# ClockDelay.net
KiCad netlist of a schematic drawn in EAGLE
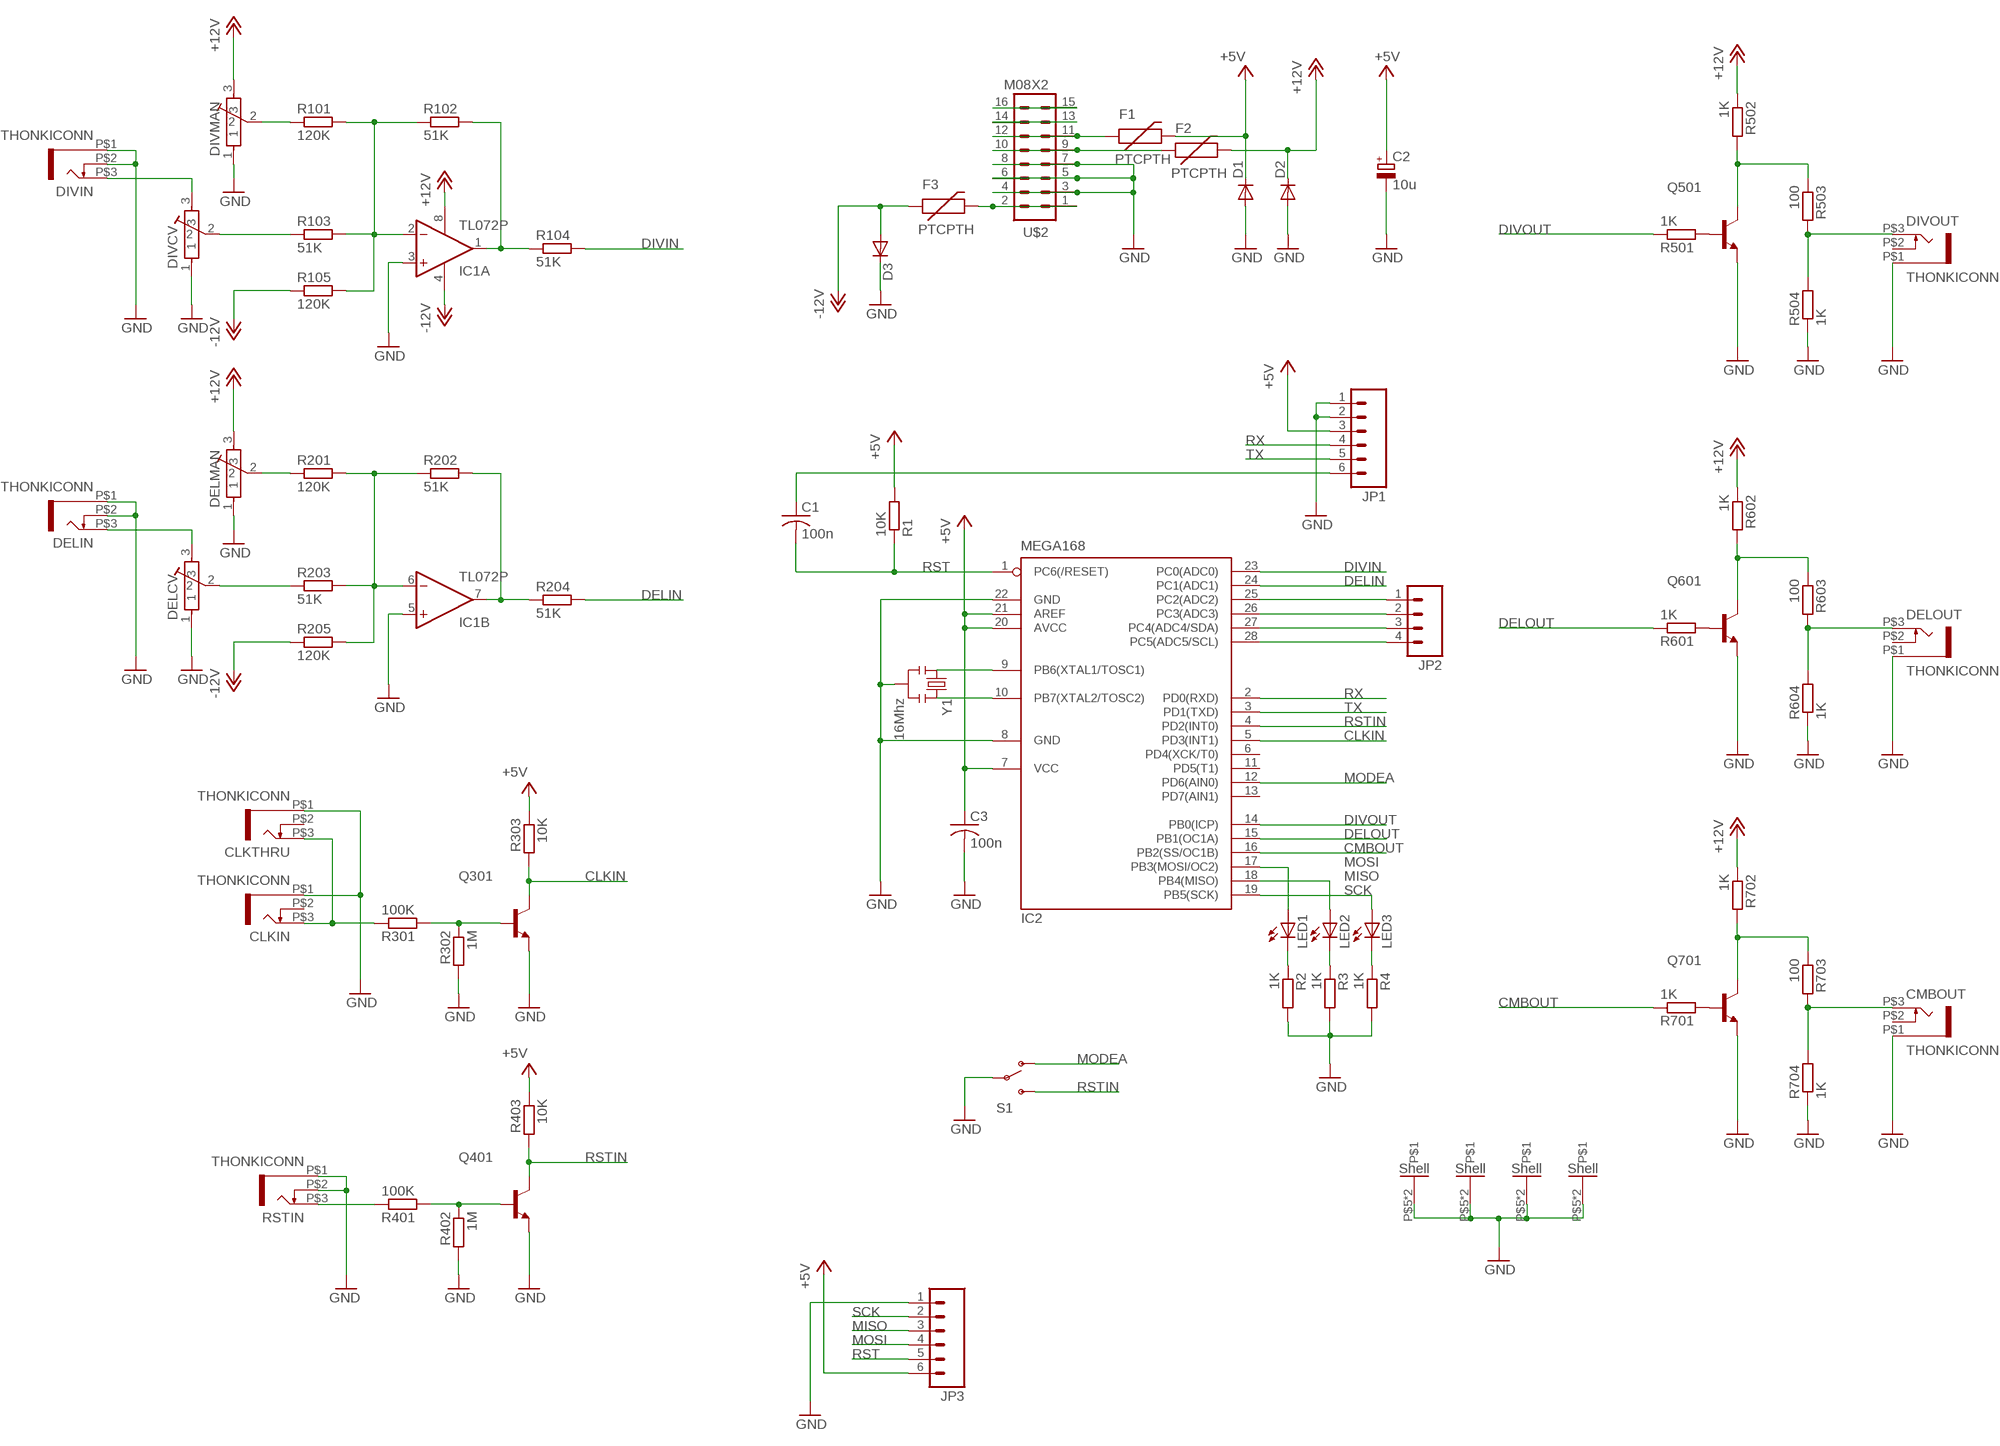
[diagram p0: schematic, sheet 1]

(export (version "E")
  (design (tool "Eeschema 10.0.6"))
  (components
    (comp (ref "C1")
      (value "100n")
      (footprint "eagle-import:C050-024X044")
      (libsource (lib "eagle-import") (part "C-US050-024X044"))
    )
    (comp (ref "C2")
      (value "10u")
      (footprint "eagle-import:E5-6")
      (libsource (lib "eagle-import") (part "CPOL-EUE5-6"))
    )
    (comp (ref "C3")
      (value "100n")
      (footprint "eagle-import:C050-024X044")
      (libsource (lib "eagle-import") (part "C-US050-024X044"))
    )
    (comp (ref "CLKIN")
      (value "THONKICONN")
      (footprint "eagle-import:THONKICONN")
      (libsource (lib "eagle-import") (part "THONKICONN"))
    )
    (comp (ref "CLKTHRU")
      (value "THONKICONN")
      (footprint "eagle-import:THONKICONN")
      (libsource (lib "eagle-import") (part "THONKICONN"))
    )
    (comp (ref "CMBOUT")
      (value "THONKICONN")
      (footprint "eagle-import:THONKICONN")
      (libsource (lib "eagle-import") (part "THONKICONN"))
    )
    (comp (ref "D1")
      (value "DIODE1N4001")
      (footprint "eagle-import:DIODE-1N4001")
      (libsource (lib "eagle-import") (part "DIODE1N4001"))
    )
    (comp (ref "D2")
      (value "DIODE1N4001")
      (footprint "eagle-import:DIODE-1N4001")
      (libsource (lib "eagle-import") (part "DIODE1N4001"))
    )
    (comp (ref "D3")
      (value "DIODE1N4001")
      (footprint "eagle-import:DIODE-1N4001")
      (libsource (lib "eagle-import") (part "DIODE1N4001"))
    )
    (comp (ref "DELCV")
      (value "POT-ALPS-RK09L1140")
      (footprint "eagle-import:POT-ALPS-RK09L1140")
      (libsource (lib "eagle-import") (part "POT-ALPS-RK09L1140"))
    )
    (comp (ref "DELIN")
      (value "THONKICONN")
      (footprint "eagle-import:THONKICONN")
      (libsource (lib "eagle-import") (part "THONKICONN"))
    )
    (comp (ref "DELMAN")
      (value "POT-ALPS-RK09L1140")
      (footprint "eagle-import:POT-ALPS-RK09L1140")
      (libsource (lib "eagle-import") (part "POT-ALPS-RK09L1140"))
    )
    (comp (ref "DELOUT")
      (value "THONKICONN")
      (footprint "eagle-import:THONKICONN")
      (libsource (lib "eagle-import") (part "THONKICONN"))
    )
    (comp (ref "DIVCV")
      (value "POT-ALPS-RK09L1140")
      (footprint "eagle-import:POT-ALPS-RK09L1140")
      (libsource (lib "eagle-import") (part "POT-ALPS-RK09L1140"))
    )
    (comp (ref "DIVIN")
      (value "THONKICONN")
      (footprint "eagle-import:THONKICONN")
      (libsource (lib "eagle-import") (part "THONKICONN"))
    )
    (comp (ref "DIVMAN")
      (value "POT-ALPS-RK09L1140")
      (footprint "eagle-import:POT-ALPS-RK09L1140")
      (libsource (lib "eagle-import") (part "POT-ALPS-RK09L1140"))
    )
    (comp (ref "DIVOUT")
      (value "THONKICONN")
      (footprint "eagle-import:THONKICONN")
      (libsource (lib "eagle-import") (part "THONKICONN"))
    )
    (comp (ref "F1")
      (value "PTCPTH")
      (footprint "eagle-import:PTC")
      (libsource (lib "eagle-import") (part "PTCPTH"))
    )
    (comp (ref "F2")
      (value "PTCPTH")
      (footprint "eagle-import:PTC")
      (libsource (lib "eagle-import") (part "PTCPTH"))
    )
    (comp (ref "F3")
      (value "PTCPTH")
      (footprint "eagle-import:PTC")
      (libsource (lib "eagle-import") (part "PTCPTH"))
    )
    (comp (ref "IC1")
      (value "TL072P")
      (footprint "eagle-import:DIL08")
      (libsource (lib "eagle-import") (part "TL072P"))
    )
    (comp (ref "IC2")
      (value "MEGA168")
      (footprint "eagle-import:DIL28-3")
      (libsource (lib "eagle-import") (part "MEGA8-P"))
    )
    (comp (ref "JP1")
      (value "M06SIP")
      (footprint "eagle-import:1X06")
      (libsource (lib "eagle-import") (part "M06SIP"))
    )
    (comp (ref "JP2")
      (value "M04PTH")
      (footprint "eagle-import:1X04")
      (libsource (lib "eagle-import") (part "M04PTH"))
    )
    (comp (ref "JP3")
      (value "M06SIP")
      (footprint "eagle-import:1X06")
      (libsource (lib "eagle-import") (part "M06SIP"))
    )
    (comp (ref "LED1")
      (value "LED3MM")
      (footprint "eagle-import:LED3MM")
      (libsource (lib "eagle-import") (part "LED3MM"))
    )
    (comp (ref "LED2")
      (value "LED3MM")
      (footprint "eagle-import:LED3MM")
      (libsource (lib "eagle-import") (part "LED3MM"))
    )
    (comp (ref "LED3")
      (value "LED3MM")
      (footprint "eagle-import:LED3MM")
      (libsource (lib "eagle-import") (part "LED3MM"))
    )
    (comp (ref "Q301")
      (value "2N3904-NPN-TO92-EBC")
      (footprint "eagle-import:TO92-EBC")
      (libsource (lib "eagle-import") (part "-NPN-TO92-EBC2N3904"))
    )
    (comp (ref "Q401")
      (value "2N3904-NPN-TO92-EBC")
      (footprint "eagle-import:TO92-EBC")
      (libsource (lib "eagle-import") (part "-NPN-TO92-EBC2N3904"))
    )
    (comp (ref "Q501")
      (value "2N3904-NPN-TO92-EBC")
      (footprint "eagle-import:TO92-EBC")
      (libsource (lib "eagle-import") (part "-NPN-TO92-EBC2N3904"))
    )
    (comp (ref "Q601")
      (value "2N3904-NPN-TO92-EBC")
      (footprint "eagle-import:TO92-EBC")
      (libsource (lib "eagle-import") (part "-NPN-TO92-EBC2N3904"))
    )
    (comp (ref "Q701")
      (value "2N3904-NPN-TO92-EBC")
      (footprint "eagle-import:TO92-EBC")
      (libsource (lib "eagle-import") (part "-NPN-TO92-EBC2N3904"))
    )
    (comp (ref "R1")
      (value "10K")
      (footprint "eagle-import:0204_7")
      (libsource (lib "eagle-import") (part "R-EU_0204/7"))
    )
    (comp (ref "R2")
      (value "1K")
      (footprint "eagle-import:0204_7")
      (libsource (lib "eagle-import") (part "R-EU_0204/7"))
    )
    (comp (ref "R3")
      (value "1K")
      (footprint "eagle-import:0204_7")
      (libsource (lib "eagle-import") (part "R-EU_0204/7"))
    )
    (comp (ref "R4")
      (value "1K")
      (footprint "eagle-import:0204_7")
      (libsource (lib "eagle-import") (part "R-EU_0204/7"))
    )
    (comp (ref "R101")
      (value "120K")
      (footprint "eagle-import:0204_7")
      (libsource (lib "eagle-import") (part "R-EU_0204/7"))
    )
    (comp (ref "R102")
      (value "51K")
      (footprint "eagle-import:0204_7")
      (libsource (lib "eagle-import") (part "R-EU_0204/7"))
    )
    (comp (ref "R103")
      (value "51K")
      (footprint "eagle-import:0204_7")
      (libsource (lib "eagle-import") (part "R-EU_0204/7"))
    )
    (comp (ref "R104")
      (value "51K")
      (footprint "eagle-import:0204_7")
      (libsource (lib "eagle-import") (part "R-EU_0204/7"))
    )
    (comp (ref "R105")
      (value "120K")
      (footprint "eagle-import:0204_7")
      (libsource (lib "eagle-import") (part "R-EU_0204/7"))
    )
    (comp (ref "R201")
      (value "120K")
      (footprint "eagle-import:0204_7")
      (libsource (lib "eagle-import") (part "R-EU_0204/7"))
    )
    (comp (ref "R202")
      (value "51K")
      (footprint "eagle-import:0204_7")
      (libsource (lib "eagle-import") (part "R-EU_0204/7"))
    )
    (comp (ref "R203")
      (value "51K")
      (footprint "eagle-import:0204_7")
      (libsource (lib "eagle-import") (part "R-EU_0204/7"))
    )
    (comp (ref "R204")
      (value "51K")
      (footprint "eagle-import:0204_7")
      (libsource (lib "eagle-import") (part "R-EU_0204/7"))
    )
    (comp (ref "R205")
      (value "120K")
      (footprint "eagle-import:0204_7")
      (libsource (lib "eagle-import") (part "R-EU_0204/7"))
    )
    (comp (ref "R301")
      (value "100K")
      (footprint "eagle-import:0204_7")
      (libsource (lib "eagle-import") (part "R-EU_0204/7"))
    )
    (comp (ref "R302")
      (value "1M")
      (footprint "eagle-import:0204_7")
      (libsource (lib "eagle-import") (part "R-EU_0204/7"))
    )
    (comp (ref "R303")
      (value "10K")
      (footprint "eagle-import:0204_7")
      (libsource (lib "eagle-import") (part "R-EU_0204/7"))
    )
    (comp (ref "R401")
      (value "100K")
      (footprint "eagle-import:0204_7")
      (libsource (lib "eagle-import") (part "R-EU_0204/7"))
    )
    (comp (ref "R402")
      (value "1M")
      (footprint "eagle-import:0204_7")
      (libsource (lib "eagle-import") (part "R-EU_0204/7"))
    )
    (comp (ref "R403")
      (value "10K")
      (footprint "eagle-import:0204_7")
      (libsource (lib "eagle-import") (part "R-EU_0204/7"))
    )
    (comp (ref "R501")
      (value "1K")
      (footprint "eagle-import:0204_7")
      (libsource (lib "eagle-import") (part "R-EU_0204/7"))
    )
    (comp (ref "R502")
      (value "1K")
      (footprint "eagle-import:0204_7")
      (libsource (lib "eagle-import") (part "R-EU_0204/7"))
    )
    (comp (ref "R503")
      (value "100")
      (footprint "eagle-import:0204_7")
      (libsource (lib "eagle-import") (part "R-EU_0204/7"))
    )
    (comp (ref "R504")
      (value "1K")
      (footprint "eagle-import:0204_7")
      (libsource (lib "eagle-import") (part "R-EU_0204/7"))
    )
    (comp (ref "R601")
      (value "1K")
      (footprint "eagle-import:0204_7")
      (libsource (lib "eagle-import") (part "R-EU_0204/7"))
    )
    (comp (ref "R602")
      (value "1K")
      (footprint "eagle-import:0204_7")
      (libsource (lib "eagle-import") (part "R-EU_0204/7"))
    )
    (comp (ref "R603")
      (value "100")
      (footprint "eagle-import:0204_7")
      (libsource (lib "eagle-import") (part "R-EU_0204/7"))
    )
    (comp (ref "R604")
      (value "1K")
      (footprint "eagle-import:0204_7")
      (libsource (lib "eagle-import") (part "R-EU_0204/7"))
    )
    (comp (ref "R701")
      (value "1K")
      (footprint "eagle-import:0204_7")
      (libsource (lib "eagle-import") (part "R-EU_0204/7"))
    )
    (comp (ref "R702")
      (value "1K")
      (footprint "eagle-import:0204_7")
      (libsource (lib "eagle-import") (part "R-EU_0204/7"))
    )
    (comp (ref "R703")
      (value "100")
      (footprint "eagle-import:0204_7")
      (libsource (lib "eagle-import") (part "R-EU_0204/7"))
    )
    (comp (ref "R704")
      (value "1K")
      (footprint "eagle-import:0204_7")
      (libsource (lib "eagle-import") (part "R-EU_0204/7"))
    )
    (comp (ref "RSTIN")
      (value "THONKICONN")
      (footprint "eagle-import:THONKICONN")
      (libsource (lib "eagle-import") (part "THONKICONN"))
    )
    (comp (ref "S1")
      (value "SWITCH-SPST")
      (footprint "eagle-import:SWITCH-SPDT-SALECOM-T8014")
      (libsource (lib "eagle-import") (part "SWITCH-SPST"))
    )
    (comp (ref "U$2")
      (value "M08X2")
      (footprint "eagle-import:2X8")
      (libsource (lib "eagle-import") (part "M08X2"))
    )
    (comp (ref "Y1")
      (value "16Mhz")
      (footprint "eagle-import:RESONATOR-PTH")
      (libsource (lib "eagle-import") (part "RESONATORPTH"))
    )
  )
  (nets
    (net (code "1") (name "+5V") (class "Default")
      (node (ref "C2") (pin "+") (pinfunction "+_+") (pintype "passive"))
      (node (ref "C3") (pin "1") (pinfunction "1_1") (pintype "passive"))
      (node (ref "D1") (pin "C") (pinfunction "C_C") (pintype "passive"))
      (node (ref "F1") (pin "P$2") (pinfunction "2_P$2") (pintype "bidirectional"))
      (node (ref "IC2") (pin "20") (pinfunction "AVCC_20") (pintype "power_in"))
      (node (ref "IC2") (pin "21") (pinfunction "AREF_21") (pintype "passive"))
      (node (ref "IC2") (pin "7") (pinfunction "VCC_7") (pintype "power_in"))
      (node (ref "JP1") (pin "3") (pinfunction "3_3") (pintype "passive"))
      (node (ref "JP3") (pin "6") (pinfunction "6_6") (pintype "passive"))
      (node (ref "R1") (pin "2") (pinfunction "2_2") (pintype "passive"))
      (node (ref "R303") (pin "1") (pinfunction "1_1") (pintype "passive"))
      (node (ref "R403") (pin "1") (pinfunction "1_1") (pintype "passive"))
    )
    (net (code "2") (name "+12V") (class "Default")
      (node (ref "D2") (pin "C") (pinfunction "C_C") (pintype "passive"))
      (node (ref "DELMAN") (pin "3") (pinfunction "3_3") (pintype "bidirectional"))
      (node (ref "DIVMAN") (pin "3") (pinfunction "3_3") (pintype "bidirectional"))
      (node (ref "F2") (pin "P$2") (pinfunction "2_P$2") (pintype "bidirectional"))
      (node (ref "IC1") (pin "8") (pinfunction "V+_8") (pintype "power_in"))
      (node (ref "R502") (pin "1") (pinfunction "1_1") (pintype "passive"))
      (node (ref "R602") (pin "1") (pinfunction "1_1") (pintype "passive"))
      (node (ref "R702") (pin "1") (pinfunction "1_1") (pintype "passive"))
    )
    (net (code "3") (name "-12V") (class "Default")
      (node (ref "D3") (pin "A") (pinfunction "A_A") (pintype "passive"))
      (node (ref "F3") (pin "P$1") (pinfunction "1_P$1") (pintype "bidirectional"))
      (node (ref "IC1") (pin "4") (pinfunction "V-_4") (pintype "power_in"))
      (node (ref "R105") (pin "1") (pinfunction "1_1") (pintype "passive"))
      (node (ref "R205") (pin "1") (pinfunction "1_1") (pintype "passive"))
    )
    (net (code "4") (name "/CLKIN") (class "Default")
      (node (ref "IC2") (pin "5") (pinfunction "PD3(INT1)_5") (pintype "bidirectional"))
      (node (ref "Q301") (pin "C") (pinfunction "C_C") (pintype "passive"))
      (node (ref "R303") (pin "2") (pinfunction "2_2") (pintype "passive"))
    )
    (net (code "5") (name "/CMBOUT") (class "Default")
      (node (ref "IC2") (pin "16") (pinfunction "PB2(SS/OC1B)_16") (pintype "bidirectional"))
      (node (ref "R701") (pin "1") (pinfunction "1_1") (pintype "passive"))
    )
    (net (code "6") (name "/DELIN") (class "Default")
      (node (ref "IC2") (pin "24") (pinfunction "PC1(ADC1)_24") (pintype "bidirectional"))
      (node (ref "R204") (pin "2") (pinfunction "2_2") (pintype "passive"))
    )
    (net (code "7") (name "/DELOUT") (class "Default")
      (node (ref "IC2") (pin "15") (pinfunction "PB1(OC1A)_15") (pintype "bidirectional"))
      (node (ref "R601") (pin "1") (pinfunction "1_1") (pintype "passive"))
    )
    (net (code "8") (name "/DIVIN") (class "Default")
      (node (ref "IC2") (pin "23") (pinfunction "PC0(ADC0)_23") (pintype "bidirectional"))
      (node (ref "R104") (pin "2") (pinfunction "2_2") (pintype "passive"))
    )
    (net (code "9") (name "/DIVOUT") (class "Default")
      (node (ref "IC2") (pin "14") (pinfunction "PB0(ICP)_14") (pintype "bidirectional"))
      (node (ref "R501") (pin "1") (pinfunction "1_1") (pintype "passive"))
    )
    (net (code "10") (name "/MISO") (class "Default")
      (node (ref "IC2") (pin "18") (pinfunction "PB4(MISO)_18") (pintype "bidirectional"))
      (node (ref "JP3") (pin "3") (pinfunction "3_3") (pintype "passive"))
      (node (ref "LED2") (pin "A") (pinfunction "A_A") (pintype "passive"))
    )
    (net (code "11") (name "/MODEA") (class "Default")
      (node (ref "IC2") (pin "12") (pinfunction "PD6(AIN0)_12") (pintype "bidirectional"))
      (node (ref "S1") (pin "1") (pinfunction "O_1") (pintype "passive"))
    )
    (net (code "12") (name "/MOSI") (class "Default")
      (node (ref "IC2") (pin "17") (pinfunction "PB3(MOSI/OC2)_17") (pintype "bidirectional"))
      (node (ref "JP3") (pin "4") (pinfunction "4_4") (pintype "passive"))
      (node (ref "LED1") (pin "A") (pinfunction "A_A") (pintype "passive"))
    )
    (net (code "13") (name "/RST") (class "Default")
      (node (ref "C1") (pin "2") (pinfunction "2_2") (pintype "passive"))
      (node (ref "IC2") (pin "1") (pinfunction "PC6(/RESET)_1") (pintype "bidirectional"))
      (node (ref "JP3") (pin "5") (pinfunction "5_5") (pintype "passive"))
      (node (ref "R1") (pin "1") (pinfunction "1_1") (pintype "passive"))
    )
    (net (code "14") (name "/RSTIN") (class "Default")
      (node (ref "IC2") (pin "4") (pinfunction "PD2(INT0)_4") (pintype "bidirectional"))
      (node (ref "Q401") (pin "C") (pinfunction "C_C") (pintype "passive"))
      (node (ref "R403") (pin "2") (pinfunction "2_2") (pintype "passive"))
      (node (ref "S1") (pin "3") (pinfunction "S_3") (pintype "passive"))
    )
    (net (code "15") (name "/RX") (class "Default")
      (node (ref "IC2") (pin "2") (pinfunction "PD0(RXD)_2") (pintype "bidirectional"))
      (node (ref "JP1") (pin "4") (pinfunction "4_4") (pintype "passive"))
    )
    (net (code "16") (name "/SCK") (class "Default")
      (node (ref "IC2") (pin "19") (pinfunction "PB5(SCK)_19") (pintype "bidirectional"))
      (node (ref "JP3") (pin "2") (pinfunction "2_2") (pintype "passive"))
      (node (ref "LED3") (pin "A") (pinfunction "A_A") (pintype "passive"))
    )
    (net (code "17") (name "/TX") (class "Default")
      (node (ref "IC2") (pin "3") (pinfunction "PD1(TXD)_3") (pintype "bidirectional"))
      (node (ref "JP1") (pin "5") (pinfunction "5_5") (pintype "passive"))
    )
    (net (code "18") (name "GND") (class "Default")
      (node (ref "C2") (pin "-") (pinfunction "-_-") (pintype "passive"))
      (node (ref "C3") (pin "2") (pinfunction "2_2") (pintype "passive"))
      (node (ref "CLKIN") (pin "P$1") (pinfunction "5_P$1") (pintype "passive"))
      (node (ref "CLKTHRU") (pin "P$1") (pinfunction "5_P$1") (pintype "passive"))
      (node (ref "CMBOUT") (pin "P$1") (pinfunction "5_P$1") (pintype "passive"))
      (node (ref "D1") (pin "A") (pinfunction "A_A") (pintype "passive"))
      (node (ref "D2") (pin "A") (pinfunction "A_A") (pintype "passive"))
      (node (ref "D3") (pin "C") (pinfunction "C_C") (pintype "passive"))
      (node (ref "DELCV") (pin "1") (pinfunction "1_1") (pintype "bidirectional"))
      (node (ref "DELCV") (pin "P$5") (pinfunction "P$1_P$5") (pintype "bidirectional"))
      (node (ref "DELCV") (pin "P$6") (pinfunction "P$1_P$6") (pintype "bidirectional"))
      (node (ref "DELIN") (pin "P$1") (pinfunction "5_P$1") (pintype "passive"))
      (node (ref "DELIN") (pin "P$2") (pinfunction "4_P$2") (pintype "passive"))
      (node (ref "DELMAN") (pin "1") (pinfunction "1_1") (pintype "bidirectional"))
      (node (ref "DELMAN") (pin "P$5") (pinfunction "P$1_P$5") (pintype "bidirectional"))
      (node (ref "DELMAN") (pin "P$6") (pinfunction "P$1_P$6") (pintype "bidirectional"))
      (node (ref "DELOUT") (pin "P$1") (pinfunction "5_P$1") (pintype "passive"))
      (node (ref "DIVCV") (pin "1") (pinfunction "1_1") (pintype "bidirectional"))
      (node (ref "DIVCV") (pin "P$5") (pinfunction "P$1_P$5") (pintype "bidirectional"))
      (node (ref "DIVCV") (pin "P$6") (pinfunction "P$1_P$6") (pintype "bidirectional"))
      (node (ref "DIVIN") (pin "P$1") (pinfunction "5_P$1") (pintype "passive"))
      (node (ref "DIVIN") (pin "P$2") (pinfunction "4_P$2") (pintype "passive"))
      (node (ref "DIVMAN") (pin "1") (pinfunction "1_1") (pintype "bidirectional"))
      (node (ref "DIVMAN") (pin "P$5") (pinfunction "P$1_P$5") (pintype "bidirectional"))
      (node (ref "DIVMAN") (pin "P$6") (pinfunction "P$1_P$6") (pintype "bidirectional"))
      (node (ref "DIVOUT") (pin "P$1") (pinfunction "5_P$1") (pintype "passive"))
      (node (ref "IC1") (pin "3") (pinfunction "+IN_3") (pintype "input"))
      (node (ref "IC1") (pin "5") (pinfunction "+IN_5") (pintype "input"))
      (node (ref "IC2") (pin "22") (pinfunction "GND_22") (pintype "power_in"))
      (node (ref "IC2") (pin "8") (pinfunction "GND_8") (pintype "power_in"))
      (node (ref "JP1") (pin "1") (pinfunction "1_1") (pintype "passive"))
      (node (ref "JP1") (pin "2") (pinfunction "2_2") (pintype "passive"))
      (node (ref "JP3") (pin "1") (pinfunction "1_1") (pintype "passive"))
      (node (ref "Q301") (pin "E") (pinfunction "E_E") (pintype "passive"))
      (node (ref "Q401") (pin "E") (pinfunction "E_E") (pintype "passive"))
      (node (ref "Q501") (pin "E") (pinfunction "E_E") (pintype "passive"))
      (node (ref "Q601") (pin "E") (pinfunction "E_E") (pintype "passive"))
      (node (ref "Q701") (pin "E") (pinfunction "E_E") (pintype "passive"))
      (node (ref "R2") (pin "2") (pinfunction "2_2") (pintype "passive"))
      (node (ref "R3") (pin "2") (pinfunction "2_2") (pintype "passive"))
      (node (ref "R302") (pin "2") (pinfunction "2_2") (pintype "passive"))
      (node (ref "R4") (pin "2") (pinfunction "2_2") (pintype "passive"))
      (node (ref "R402") (pin "2") (pinfunction "2_2") (pintype "passive"))
      (node (ref "R504") (pin "1") (pinfunction "1_1") (pintype "passive"))
      (node (ref "R604") (pin "1") (pinfunction "1_1") (pintype "passive"))
      (node (ref "R704") (pin "1") (pinfunction "1_1") (pintype "passive"))
      (node (ref "RSTIN") (pin "P$1") (pinfunction "5_P$1") (pintype "passive"))
      (node (ref "RSTIN") (pin "P$2") (pinfunction "4_P$2") (pintype "passive"))
      (node (ref "S1") (pin "2") (pinfunction "P_2") (pintype "passive"))
      (node (ref "U$2") (pin "3") (pinfunction "3_3") (pintype "passive"))
      (node (ref "U$2") (pin "4") (pinfunction "4_4") (pintype "passive"))
      (node (ref "U$2") (pin "5") (pinfunction "5_5") (pintype "passive"))
      (node (ref "U$2") (pin "6") (pinfunction "6_6") (pintype "passive"))
      (node (ref "U$2") (pin "7") (pinfunction "7_7") (pintype "passive"))
      (node (ref "U$2") (pin "8") (pinfunction "8_8") (pintype "passive"))
      (node (ref "Y1") (pin "2") (pinfunction "2_2") (pintype "passive"))
    )
    (net (code "19") (name "Net-(C1-Pad1)") (class "Default")
      (node (ref "C1") (pin "1") (pinfunction "1_1") (pintype "passive"))
      (node (ref "JP1") (pin "6") (pinfunction "6_6") (pintype "passive"))
    )
    (net (code "20") (name "Net-(CLKIN-3)") (class "Default")
      (node (ref "CLKIN") (pin "P$3") (pinfunction "3_P$3") (pintype "passive"))
      (node (ref "CLKTHRU") (pin "P$3") (pinfunction "3_P$3") (pintype "passive"))
      (node (ref "R301") (pin "1") (pinfunction "1_1") (pintype "passive"))
    )
    (net (code "21") (name "Net-(CMBOUT-3)") (class "Default")
      (node (ref "CMBOUT") (pin "P$3") (pinfunction "3_P$3") (pintype "passive"))
      (node (ref "R703") (pin "2") (pinfunction "2_2") (pintype "passive"))
      (node (ref "R704") (pin "2") (pinfunction "2_2") (pintype "passive"))
    )
    (net (code "22") (name "Net-(DELCV-Pad2)") (class "Default")
      (node (ref "DELCV") (pin "2") (pinfunction "2_2") (pintype "bidirectional"))
      (node (ref "R203") (pin "1") (pinfunction "1_1") (pintype "passive"))
    )
    (net (code "23") (name "Net-(DELIN-3)") (class "Default")
      (node (ref "DELCV") (pin "3") (pinfunction "3_3") (pintype "bidirectional"))
      (node (ref "DELIN") (pin "P$3") (pinfunction "3_P$3") (pintype "passive"))
    )
    (net (code "24") (name "Net-(DELMAN-Pad2)") (class "Default")
      (node (ref "DELMAN") (pin "2") (pinfunction "2_2") (pintype "bidirectional"))
      (node (ref "R201") (pin "1") (pinfunction "1_1") (pintype "passive"))
    )
    (net (code "25") (name "Net-(DELOUT-3)") (class "Default")
      (node (ref "DELOUT") (pin "P$3") (pinfunction "3_P$3") (pintype "passive"))
      (node (ref "R603") (pin "2") (pinfunction "2_2") (pintype "passive"))
      (node (ref "R604") (pin "2") (pinfunction "2_2") (pintype "passive"))
    )
    (net (code "26") (name "Net-(DIVCV-Pad2)") (class "Default")
      (node (ref "DIVCV") (pin "2") (pinfunction "2_2") (pintype "bidirectional"))
      (node (ref "R103") (pin "1") (pinfunction "1_1") (pintype "passive"))
    )
    (net (code "27") (name "Net-(DIVIN-3)") (class "Default")
      (node (ref "DIVCV") (pin "3") (pinfunction "3_3") (pintype "bidirectional"))
      (node (ref "DIVIN") (pin "P$3") (pinfunction "3_P$3") (pintype "passive"))
    )
    (net (code "28") (name "Net-(DIVMAN-Pad2)") (class "Default")
      (node (ref "DIVMAN") (pin "2") (pinfunction "2_2") (pintype "bidirectional"))
      (node (ref "R101") (pin "1") (pinfunction "1_1") (pintype "passive"))
    )
    (net (code "29") (name "Net-(DIVOUT-3)") (class "Default")
      (node (ref "DIVOUT") (pin "P$3") (pinfunction "3_P$3") (pintype "passive"))
      (node (ref "R503") (pin "2") (pinfunction "2_2") (pintype "passive"))
      (node (ref "R504") (pin "2") (pinfunction "2_2") (pintype "passive"))
    )
    (net (code "30") (name "Net-(F1-1)") (class "Default")
      (node (ref "F1") (pin "P$1") (pinfunction "1_P$1") (pintype "bidirectional"))
      (node (ref "U$2") (pin "11") (pinfunction "11_11") (pintype "passive"))
      (node (ref "U$2") (pin "12") (pinfunction "12_12") (pintype "passive"))
    )
    (net (code "31") (name "Net-(F2-1)") (class "Default")
      (node (ref "F2") (pin "P$1") (pinfunction "1_P$1") (pintype "bidirectional"))
      (node (ref "U$2") (pin "10") (pinfunction "10_10") (pintype "passive"))
      (node (ref "U$2") (pin "9") (pinfunction "9_9") (pintype "passive"))
    )
    (net (code "32") (name "Net-(F3-2)") (class "Default")
      (node (ref "F3") (pin "P$2") (pinfunction "2_P$2") (pintype "bidirectional"))
      (node (ref "U$2") (pin "1") (pinfunction "1_1") (pintype "passive"))
      (node (ref "U$2") (pin "2") (pinfunction "2_2") (pintype "passive"))
    )
    (net (code "33") (name "Net-(IC1A--IN)") (class "Default")
      (node (ref "IC1") (pin "2") (pinfunction "-IN_2") (pintype "input"))
      (node (ref "R101") (pin "2") (pinfunction "2_2") (pintype "passive"))
      (node (ref "R102") (pin "1") (pinfunction "1_1") (pintype "passive"))
      (node (ref "R103") (pin "2") (pinfunction "2_2") (pintype "passive"))
      (node (ref "R105") (pin "2") (pinfunction "2_2") (pintype "passive"))
    )
    (net (code "34") (name "Net-(IC1A-OUT)") (class "Default")
      (node (ref "IC1") (pin "1") (pinfunction "OUT_1") (pintype "output"))
      (node (ref "R102") (pin "2") (pinfunction "2_2") (pintype "passive"))
      (node (ref "R104") (pin "1") (pinfunction "1_1") (pintype "passive"))
    )
    (net (code "35") (name "Net-(IC1B--IN)") (class "Default")
      (node (ref "IC1") (pin "6") (pinfunction "-IN_6") (pintype "input"))
      (node (ref "R201") (pin "2") (pinfunction "2_2") (pintype "passive"))
      (node (ref "R202") (pin "1") (pinfunction "1_1") (pintype "passive"))
      (node (ref "R203") (pin "2") (pinfunction "2_2") (pintype "passive"))
      (node (ref "R205") (pin "2") (pinfunction "2_2") (pintype "passive"))
    )
    (net (code "36") (name "Net-(IC1B-OUT)") (class "Default")
      (node (ref "IC1") (pin "7") (pinfunction "OUT_7") (pintype "output"))
      (node (ref "R202") (pin "2") (pinfunction "2_2") (pintype "passive"))
      (node (ref "R204") (pin "1") (pinfunction "1_1") (pintype "passive"))
    )
    (net (code "37") (name "Net-(IC2-PB6(XTAL1{slash}TOSC1))") (class "Default")
      (node (ref "IC2") (pin "9") (pinfunction "PB6(XTAL1/TOSC1)_9") (pintype "bidirectional"))
      (node (ref "Y1") (pin "1") (pinfunction "1_1") (pintype "passive"))
    )
    (net (code "38") (name "Net-(IC2-PB7(XTAL2{slash}TOSC2))") (class "Default")
      (node (ref "IC2") (pin "10") (pinfunction "PB7(XTAL2/TOSC2)_10") (pintype "bidirectional"))
      (node (ref "Y1") (pin "3") (pinfunction "3_3") (pintype "passive"))
    )
    (net (code "39") (name "Net-(IC2-PC2(ADC2))") (class "Default")
      (node (ref "IC2") (pin "25") (pinfunction "PC2(ADC2)_25") (pintype "bidirectional"))
      (node (ref "JP2") (pin "1") (pinfunction "1_1") (pintype "passive"))
    )
    (net (code "40") (name "Net-(IC2-PC3(ADC3))") (class "Default")
      (node (ref "IC2") (pin "26") (pinfunction "PC3(ADC3)_26") (pintype "bidirectional"))
      (node (ref "JP2") (pin "2") (pinfunction "2_2") (pintype "passive"))
    )
    (net (code "41") (name "Net-(IC2-PC4(ADC4{slash}SDA))") (class "Default")
      (node (ref "IC2") (pin "27") (pinfunction "PC4(ADC4/SDA)_27") (pintype "bidirectional"))
      (node (ref "JP2") (pin "3") (pinfunction "3_3") (pintype "passive"))
    )
    (net (code "42") (name "Net-(IC2-PC5(ADC5{slash}SCL))") (class "Default")
      (node (ref "IC2") (pin "28") (pinfunction "PC5(ADC5/SCL)_28") (pintype "bidirectional"))
      (node (ref "JP2") (pin "4") (pinfunction "4_4") (pintype "passive"))
    )
    (net (code "43") (name "Net-(LED1-C)") (class "Default")
      (node (ref "LED1") (pin "K") (pinfunction "C_K") (pintype "passive"))
      (node (ref "R2") (pin "1") (pinfunction "1_1") (pintype "passive"))
    )
    (net (code "44") (name "Net-(LED2-C)") (class "Default")
      (node (ref "LED2") (pin "K") (pinfunction "C_K") (pintype "passive"))
      (node (ref "R3") (pin "1") (pinfunction "1_1") (pintype "passive"))
    )
    (net (code "45") (name "Net-(LED3-C)") (class "Default")
      (node (ref "LED3") (pin "K") (pinfunction "C_K") (pintype "passive"))
      (node (ref "R4") (pin "1") (pinfunction "1_1") (pintype "passive"))
    )
    (net (code "46") (name "Net-(Q301-PadB)") (class "Default")
      (node (ref "Q301") (pin "B") (pinfunction "B_B") (pintype "passive"))
      (node (ref "R301") (pin "2") (pinfunction "2_2") (pintype "passive"))
      (node (ref "R302") (pin "1") (pinfunction "1_1") (pintype "passive"))
    )
    (net (code "47") (name "Net-(Q401-PadB)") (class "Default")
      (node (ref "Q401") (pin "B") (pinfunction "B_B") (pintype "passive"))
      (node (ref "R401") (pin "2") (pinfunction "2_2") (pintype "passive"))
      (node (ref "R402") (pin "1") (pinfunction "1_1") (pintype "passive"))
    )
    (net (code "48") (name "Net-(Q501-PadB)") (class "Default")
      (node (ref "Q501") (pin "B") (pinfunction "B_B") (pintype "passive"))
      (node (ref "R501") (pin "2") (pinfunction "2_2") (pintype "passive"))
    )
    (net (code "49") (name "Net-(Q501-PadC)") (class "Default")
      (node (ref "Q501") (pin "C") (pinfunction "C_C") (pintype "passive"))
      (node (ref "R502") (pin "2") (pinfunction "2_2") (pintype "passive"))
      (node (ref "R503") (pin "1") (pinfunction "1_1") (pintype "passive"))
    )
    (net (code "50") (name "Net-(Q601-PadB)") (class "Default")
      (node (ref "Q601") (pin "B") (pinfunction "B_B") (pintype "passive"))
      (node (ref "R601") (pin "2") (pinfunction "2_2") (pintype "passive"))
    )
    (net (code "51") (name "Net-(Q601-PadC)") (class "Default")
      (node (ref "Q601") (pin "C") (pinfunction "C_C") (pintype "passive"))
      (node (ref "R602") (pin "2") (pinfunction "2_2") (pintype "passive"))
      (node (ref "R603") (pin "1") (pinfunction "1_1") (pintype "passive"))
    )
    (net (code "52") (name "Net-(Q701-PadB)") (class "Default")
      (node (ref "Q701") (pin "B") (pinfunction "B_B") (pintype "passive"))
      (node (ref "R701") (pin "2") (pinfunction "2_2") (pintype "passive"))
    )
    (net (code "53") (name "Net-(Q701-PadC)") (class "Default")
      (node (ref "Q701") (pin "C") (pinfunction "C_C") (pintype "passive"))
      (node (ref "R702") (pin "2") (pinfunction "2_2") (pintype "passive"))
      (node (ref "R703") (pin "1") (pinfunction "1_1") (pintype "passive"))
    )
    (net (code "54") (name "Net-(RSTIN-3)") (class "Default")
      (node (ref "R401") (pin "1") (pinfunction "1_1") (pintype "passive"))
      (node (ref "RSTIN") (pin "P$3") (pinfunction "3_P$3") (pintype "passive"))
    )
    (net (code "55") (name "Net-(U$2-Pad13)") (class "Default")
      (node (ref "U$2") (pin "13") (pinfunction "13_13") (pintype "passive"))
      (node (ref "U$2") (pin "14") (pinfunction "14_14") (pintype "passive"))
    )
    (net (code "56") (name "Net-(U$2-Pad15)") (class "Default")
      (node (ref "U$2") (pin "15") (pinfunction "15_15") (pintype "passive"))
      (node (ref "U$2") (pin "16") (pinfunction "16_16") (pintype "passive"))
    )
    (net (code "57") (name "unconnected-(CLKIN-4-PadP$2)") (class "Default")
      (node (ref "CLKIN") (pin "P$2") (pinfunction "4_P$2") (pintype "passive"))
    )
    (net (code "58") (name "unconnected-(CLKTHRU-4-PadP$2)") (class "Default")
      (node (ref "CLKTHRU") (pin "P$2") (pinfunction "4_P$2") (pintype "passive"))
    )
    (net (code "59") (name "unconnected-(CMBOUT-4-PadP$2)") (class "Default")
      (node (ref "CMBOUT") (pin "P$2") (pinfunction "4_P$2") (pintype "passive"))
    )
    (net (code "60") (name "unconnected-(DELOUT-4-PadP$2)") (class "Default")
      (node (ref "DELOUT") (pin "P$2") (pinfunction "4_P$2") (pintype "passive"))
    )
    (net (code "61") (name "unconnected-(DIVOUT-4-PadP$2)") (class "Default")
      (node (ref "DIVOUT") (pin "P$2") (pinfunction "4_P$2") (pintype "passive"))
    )
    (net (code "62") (name "unconnected-(IC2-PD4(XCK{slash}T0)-Pad6)") (class "Default")
      (node (ref "IC2") (pin "6") (pinfunction "PD4(XCK/T0)_6") (pintype "bidirectional"))
    )
    (net (code "63") (name "unconnected-(IC2-PD5(T1)-Pad11)") (class "Default")
      (node (ref "IC2") (pin "11") (pinfunction "PD5(T1)_11") (pintype "bidirectional"))
    )
    (net (code "64") (name "unconnected-(IC2-PD7(AIN1)-Pad13)") (class "Default")
      (node (ref "IC2") (pin "13") (pinfunction "PD7(AIN1)_13") (pintype "bidirectional"))
    )
  )
)
